# screenSlave.net
KiCad netlist of a schematic drawn in EAGLE
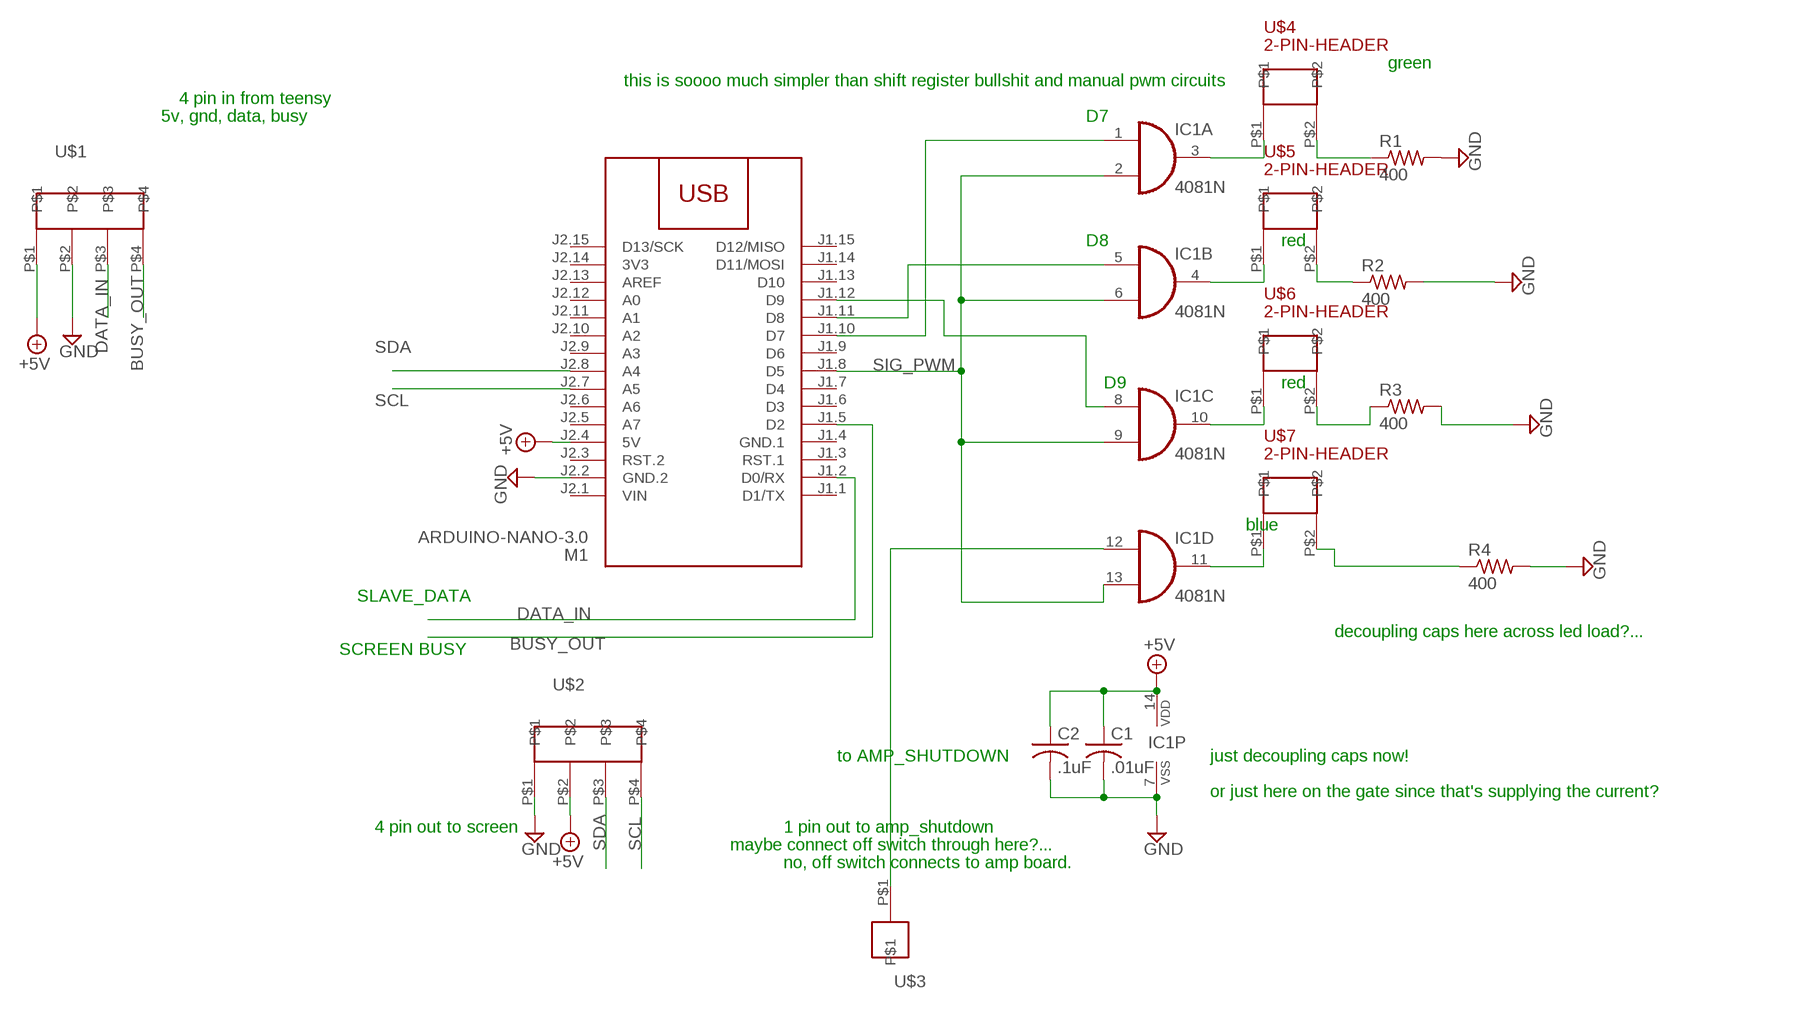
[diagram p0: schematic, sheet 1]

(export (version "E")
  (design (tool "Eeschema 10.0.6"))
  (components
    (comp (ref "C1")
      (value ".01uF")
      (footprint "eagle-import:C025-024X044")
      (libsource (lib "eagle-import") (part "C-US025-024X044"))
    )
    (comp (ref "C2")
      (value ".1uF")
      (footprint "eagle-import:C025-024X044")
      (libsource (lib "eagle-import") (part "C-US025-024X044"))
    )
    (comp (ref "IC1")
      (value "4081N")
      (footprint "eagle-import:DIL14")
      (libsource (lib "eagle-import") (part "4081N"))
    )
    (comp (ref "M1")
      (value "ARDUINO-NANO-3.0")
      (footprint "eagle-import:ARDUINO-NANO-3.0")
      (libsource (lib "eagle-import") (part "ARDUINO-NANO-3.0"))
    )
    (comp (ref "R1")
      (value "400")
      (footprint "eagle-import:0204_7")
      (libsource (lib "eagle-import") (part "R-US_0204/7"))
    )
    (comp (ref "R2")
      (value "400")
      (footprint "eagle-import:0204_7")
      (libsource (lib "eagle-import") (part "R-US_0204/7"))
    )
    (comp (ref "R3")
      (value "400")
      (footprint "eagle-import:0204_7")
      (libsource (lib "eagle-import") (part "R-US_0204/7"))
    )
    (comp (ref "R4")
      (value "400")
      (footprint "eagle-import:0204_7")
      (libsource (lib "eagle-import") (part "R-US_0204/7"))
    )
    (comp (ref "U$1")
      (value "4-PIN-HEADER")
      (footprint "eagle-import:4-PIN-HEADER")
      (libsource (lib "eagle-import") (part "4-PIN-HEADER"))
    )
    (comp (ref "U$2")
      (value "4-PIN-HEADER")
      (footprint "eagle-import:4-PIN-HEADER")
      (libsource (lib "eagle-import") (part "4-PIN-HEADER"))
    )
    (comp (ref "U$3")
      (value "1-PIN-HEADER")
      (footprint "eagle-import:1-PIN-HEADER")
      (libsource (lib "eagle-import") (part "1-PIN-HEADER"))
    )
    (comp (ref "U$4")
      (value "2-PIN-HEADER")
      (footprint "eagle-import:2-PIN-HEADER")
      (libsource (lib "eagle-import") (part "2-PIN-HEADER"))
    )
    (comp (ref "U$5")
      (value "2-PIN-HEADER")
      (footprint "eagle-import:2-PIN-HEADER")
      (libsource (lib "eagle-import") (part "2-PIN-HEADER"))
    )
    (comp (ref "U$6")
      (value "2-PIN-HEADER")
      (footprint "eagle-import:2-PIN-HEADER")
      (libsource (lib "eagle-import") (part "2-PIN-HEADER"))
    )
    (comp (ref "U$7")
      (value "2-PIN-HEADER")
      (footprint "eagle-import:2-PIN-HEADER")
      (libsource (lib "eagle-import") (part "2-PIN-HEADER"))
    )
  )
  (nets
    (net (code "1") (name "+5V") (class "Default")
      (node (ref "C1") (pin "1") (pinfunction "1_1") (pintype "passive"))
      (node (ref "C2") (pin "1") (pinfunction "1_1") (pintype "passive"))
      (node (ref "IC1") (pin "14") (pinfunction "VDD_14") (pintype "power_in"))
      (node (ref "M1") (pin "J2.4") (pinfunction "5V_J2.4") (pintype "power_in"))
      (node (ref "U$1") (pin "P$1") (pinfunction "P$1_P$1") (pintype "bidirectional"))
      (node (ref "U$2") (pin "P$2") (pinfunction "P$2_P$2") (pintype "bidirectional"))
    )
    (net (code "2") (name "/3V3") (class "Default")
      (node (ref "M1") (pin "J2.14") (pinfunction "3V3_J2.14") (pintype "power_in"))
    )
    (net (code "3") (name "/BUSY_OUT") (class "Default")
      (node (ref "M1") (pin "J1.5") (pinfunction "D2_J1.5") (pintype "bidirectional"))
      (node (ref "U$1") (pin "P$4") (pinfunction "P$4_P$4") (pintype "bidirectional"))
    )
    (net (code "4") (name "/DATA_IN") (class "Default")
      (node (ref "M1") (pin "J1.2") (pinfunction "D0/RX_J1.2") (pintype "bidirectional"))
      (node (ref "U$1") (pin "P$3") (pinfunction "P$3_P$3") (pintype "bidirectional"))
    )
    (net (code "5") (name "/GND.1") (class "Default")
      (node (ref "M1") (pin "J1.4") (pinfunction "GND.1_J1.4") (pintype "power_in"))
    )
    (net (code "6") (name "/SCL") (class "Default")
      (node (ref "M1") (pin "J2.7") (pinfunction "A5_J2.7") (pintype "bidirectional"))
      (node (ref "U$2") (pin "P$4") (pinfunction "P$4_P$4") (pintype "bidirectional"))
    )
    (net (code "7") (name "/SDA") (class "Default")
      (node (ref "M1") (pin "J2.8") (pinfunction "A4_J2.8") (pintype "bidirectional"))
      (node (ref "U$2") (pin "P$3") (pinfunction "P$3_P$3") (pintype "bidirectional"))
    )
    (net (code "8") (name "/SIG_PWM") (class "Default")
      (node (ref "IC1") (pin "13") (pinfunction "I1_13") (pintype "input"))
      (node (ref "IC1") (pin "2") (pinfunction "I1_2") (pintype "input"))
      (node (ref "IC1") (pin "6") (pinfunction "I1_6") (pintype "input"))
      (node (ref "IC1") (pin "9") (pinfunction "I1_9") (pintype "input"))
      (node (ref "M1") (pin "J1.8") (pinfunction "D5_J1.8") (pintype "bidirectional"))
    )
    (net (code "9") (name "/VIN") (class "Default")
      (node (ref "M1") (pin "J2.1") (pinfunction "VIN_J2.1") (pintype "power_in"))
    )
    (net (code "10") (name "GND") (class "Default")
      (node (ref "C1") (pin "2") (pinfunction "2_2") (pintype "passive"))
      (node (ref "C2") (pin "2") (pinfunction "2_2") (pintype "passive"))
      (node (ref "IC1") (pin "7") (pinfunction "VSS_7") (pintype "power_in"))
      (node (ref "M1") (pin "J2.2") (pinfunction "GND.2_J2.2") (pintype "power_in"))
      (node (ref "R1") (pin "2") (pinfunction "2_2") (pintype "passive"))
      (node (ref "R2") (pin "2") (pinfunction "2_2") (pintype "passive"))
      (node (ref "R3") (pin "2") (pinfunction "2_2") (pintype "passive"))
      (node (ref "R4") (pin "2") (pinfunction "2_2") (pintype "passive"))
      (node (ref "U$1") (pin "P$2") (pinfunction "P$2_P$2") (pintype "bidirectional"))
      (node (ref "U$2") (pin "P$1") (pinfunction "P$1_P$1") (pintype "bidirectional"))
    )
    (net (code "11") (name "Net-(IC1A-I0)") (class "Default")
      (node (ref "IC1") (pin "1") (pinfunction "I0_1") (pintype "input"))
      (node (ref "M1") (pin "J1.10") (pinfunction "D7_J1.10") (pintype "bidirectional"))
    )
    (net (code "12") (name "Net-(IC1A-O)") (class "Default")
      (node (ref "IC1") (pin "3") (pinfunction "O_3") (pintype "output"))
      (node (ref "U$4") (pin "P$1") (pinfunction "P$1_P$1") (pintype "bidirectional"))
    )
    (net (code "13") (name "Net-(IC1B-I0)") (class "Default")
      (node (ref "IC1") (pin "5") (pinfunction "I0_5") (pintype "input"))
      (node (ref "M1") (pin "J1.11") (pinfunction "D8_J1.11") (pintype "bidirectional"))
    )
    (net (code "14") (name "Net-(IC1B-O)") (class "Default")
      (node (ref "IC1") (pin "4") (pinfunction "O_4") (pintype "output"))
      (node (ref "U$5") (pin "P$1") (pinfunction "P$1_P$1") (pintype "bidirectional"))
    )
    (net (code "15") (name "Net-(IC1C-I0)") (class "Default")
      (node (ref "IC1") (pin "8") (pinfunction "I0_8") (pintype "input"))
      (node (ref "M1") (pin "J1.12") (pinfunction "D9_J1.12") (pintype "bidirectional"))
    )
    (net (code "16") (name "Net-(IC1C-O)") (class "Default")
      (node (ref "IC1") (pin "10") (pinfunction "O_10") (pintype "output"))
      (node (ref "U$6") (pin "P$1") (pinfunction "P$1_P$1") (pintype "bidirectional"))
    )
    (net (code "17") (name "Net-(IC1D-I0)") (class "Default")
      (node (ref "IC1") (pin "12") (pinfunction "I0_12") (pintype "input"))
      (node (ref "U$3") (pin "P$1") (pinfunction "P$1_P$1") (pintype "bidirectional"))
    )
    (net (code "18") (name "Net-(IC1D-O)") (class "Default")
      (node (ref "IC1") (pin "11") (pinfunction "O_11") (pintype "output"))
      (node (ref "U$7") (pin "P$1") (pinfunction "P$1_P$1") (pintype "bidirectional"))
    )
    (net (code "19") (name "Net-(R1-Pad1)") (class "Default")
      (node (ref "R1") (pin "1") (pinfunction "1_1") (pintype "passive"))
      (node (ref "U$4") (pin "P$2") (pinfunction "P$2_P$2") (pintype "bidirectional"))
    )
    (net (code "20") (name "Net-(R2-Pad1)") (class "Default")
      (node (ref "R2") (pin "1") (pinfunction "1_1") (pintype "passive"))
      (node (ref "U$5") (pin "P$2") (pinfunction "P$2_P$2") (pintype "bidirectional"))
    )
    (net (code "21") (name "Net-(R3-Pad1)") (class "Default")
      (node (ref "R3") (pin "1") (pinfunction "1_1") (pintype "passive"))
      (node (ref "U$6") (pin "P$2") (pinfunction "P$2_P$2") (pintype "bidirectional"))
    )
    (net (code "22") (name "Net-(R4-Pad1)") (class "Default")
      (node (ref "R4") (pin "1") (pinfunction "1_1") (pintype "passive"))
      (node (ref "U$7") (pin "P$2") (pinfunction "P$2_P$2") (pintype "bidirectional"))
    )
    (net (code "23") (name "unconnected-(M1-A0-PadJ2.12)") (class "Default")
      (node (ref "M1") (pin "J2.12") (pinfunction "A0_J2.12") (pintype "bidirectional"))
    )
    (net (code "24") (name "unconnected-(M1-A1-PadJ2.11)") (class "Default")
      (node (ref "M1") (pin "J2.11") (pinfunction "A1_J2.11") (pintype "bidirectional"))
    )
    (net (code "25") (name "unconnected-(M1-A2-PadJ2.10)") (class "Default")
      (node (ref "M1") (pin "J2.10") (pinfunction "A2_J2.10") (pintype "bidirectional"))
    )
    (net (code "26") (name "unconnected-(M1-A3-PadJ2.9)") (class "Default")
      (node (ref "M1") (pin "J2.9") (pinfunction "A3_J2.9") (pintype "bidirectional"))
    )
    (net (code "27") (name "unconnected-(M1-A6-PadJ2.6)") (class "Default")
      (node (ref "M1") (pin "J2.6") (pinfunction "A6_J2.6") (pintype "bidirectional"))
    )
    (net (code "28") (name "unconnected-(M1-A7-PadJ2.5)") (class "Default")
      (node (ref "M1") (pin "J2.5") (pinfunction "A7_J2.5") (pintype "bidirectional"))
    )
    (net (code "29") (name "unconnected-(M1-AREF-PadJ2.13)") (class "Default")
      (node (ref "M1") (pin "J2.13") (pinfunction "AREF_J2.13") (pintype "bidirectional"))
    )
    (net (code "30") (name "unconnected-(M1-D1{slash}TX-PadJ1.1)") (class "Default")
      (node (ref "M1") (pin "J1.1") (pinfunction "D1/TX_J1.1") (pintype "bidirectional"))
    )
    (net (code "31") (name "unconnected-(M1-D3-PadJ1.6)") (class "Default")
      (node (ref "M1") (pin "J1.6") (pinfunction "D3_J1.6") (pintype "bidirectional"))
    )
    (net (code "32") (name "unconnected-(M1-D4-PadJ1.7)") (class "Default")
      (node (ref "M1") (pin "J1.7") (pinfunction "D4_J1.7") (pintype "bidirectional"))
    )
    (net (code "33") (name "unconnected-(M1-D6-PadJ1.9)") (class "Default")
      (node (ref "M1") (pin "J1.9") (pinfunction "D6_J1.9") (pintype "bidirectional"))
    )
    (net (code "34") (name "unconnected-(M1-D10-PadJ1.13)") (class "Default")
      (node (ref "M1") (pin "J1.13") (pinfunction "D10_J1.13") (pintype "bidirectional"))
    )
    (net (code "35") (name "unconnected-(M1-D11{slash}MOSI-PadJ1.14)") (class "Default")
      (node (ref "M1") (pin "J1.14") (pinfunction "D11/MOSI_J1.14") (pintype "bidirectional"))
    )
    (net (code "36") (name "unconnected-(M1-D12{slash}MISO-PadJ1.15)") (class "Default")
      (node (ref "M1") (pin "J1.15") (pinfunction "D12/MISO_J1.15") (pintype "bidirectional"))
    )
    (net (code "37") (name "unconnected-(M1-D13{slash}SCK-PadJ2.15)") (class "Default")
      (node (ref "M1") (pin "J2.15") (pinfunction "D13/SCK_J2.15") (pintype "bidirectional"))
    )
    (net (code "38") (name "unconnected-(M1-RST.1-PadJ1.3)") (class "Default")
      (node (ref "M1") (pin "J1.3") (pinfunction "RST.1_J1.3") (pintype "bidirectional"))
    )
    (net (code "39") (name "unconnected-(M1-RST.2-PadJ2.3)") (class "Default")
      (node (ref "M1") (pin "J2.3") (pinfunction "RST.2_J2.3") (pintype "bidirectional"))
    )
  )
)
